# Adapter_USB3_to_M2_E.net
KiCad netlist of a schematic drawn in Altium Designer
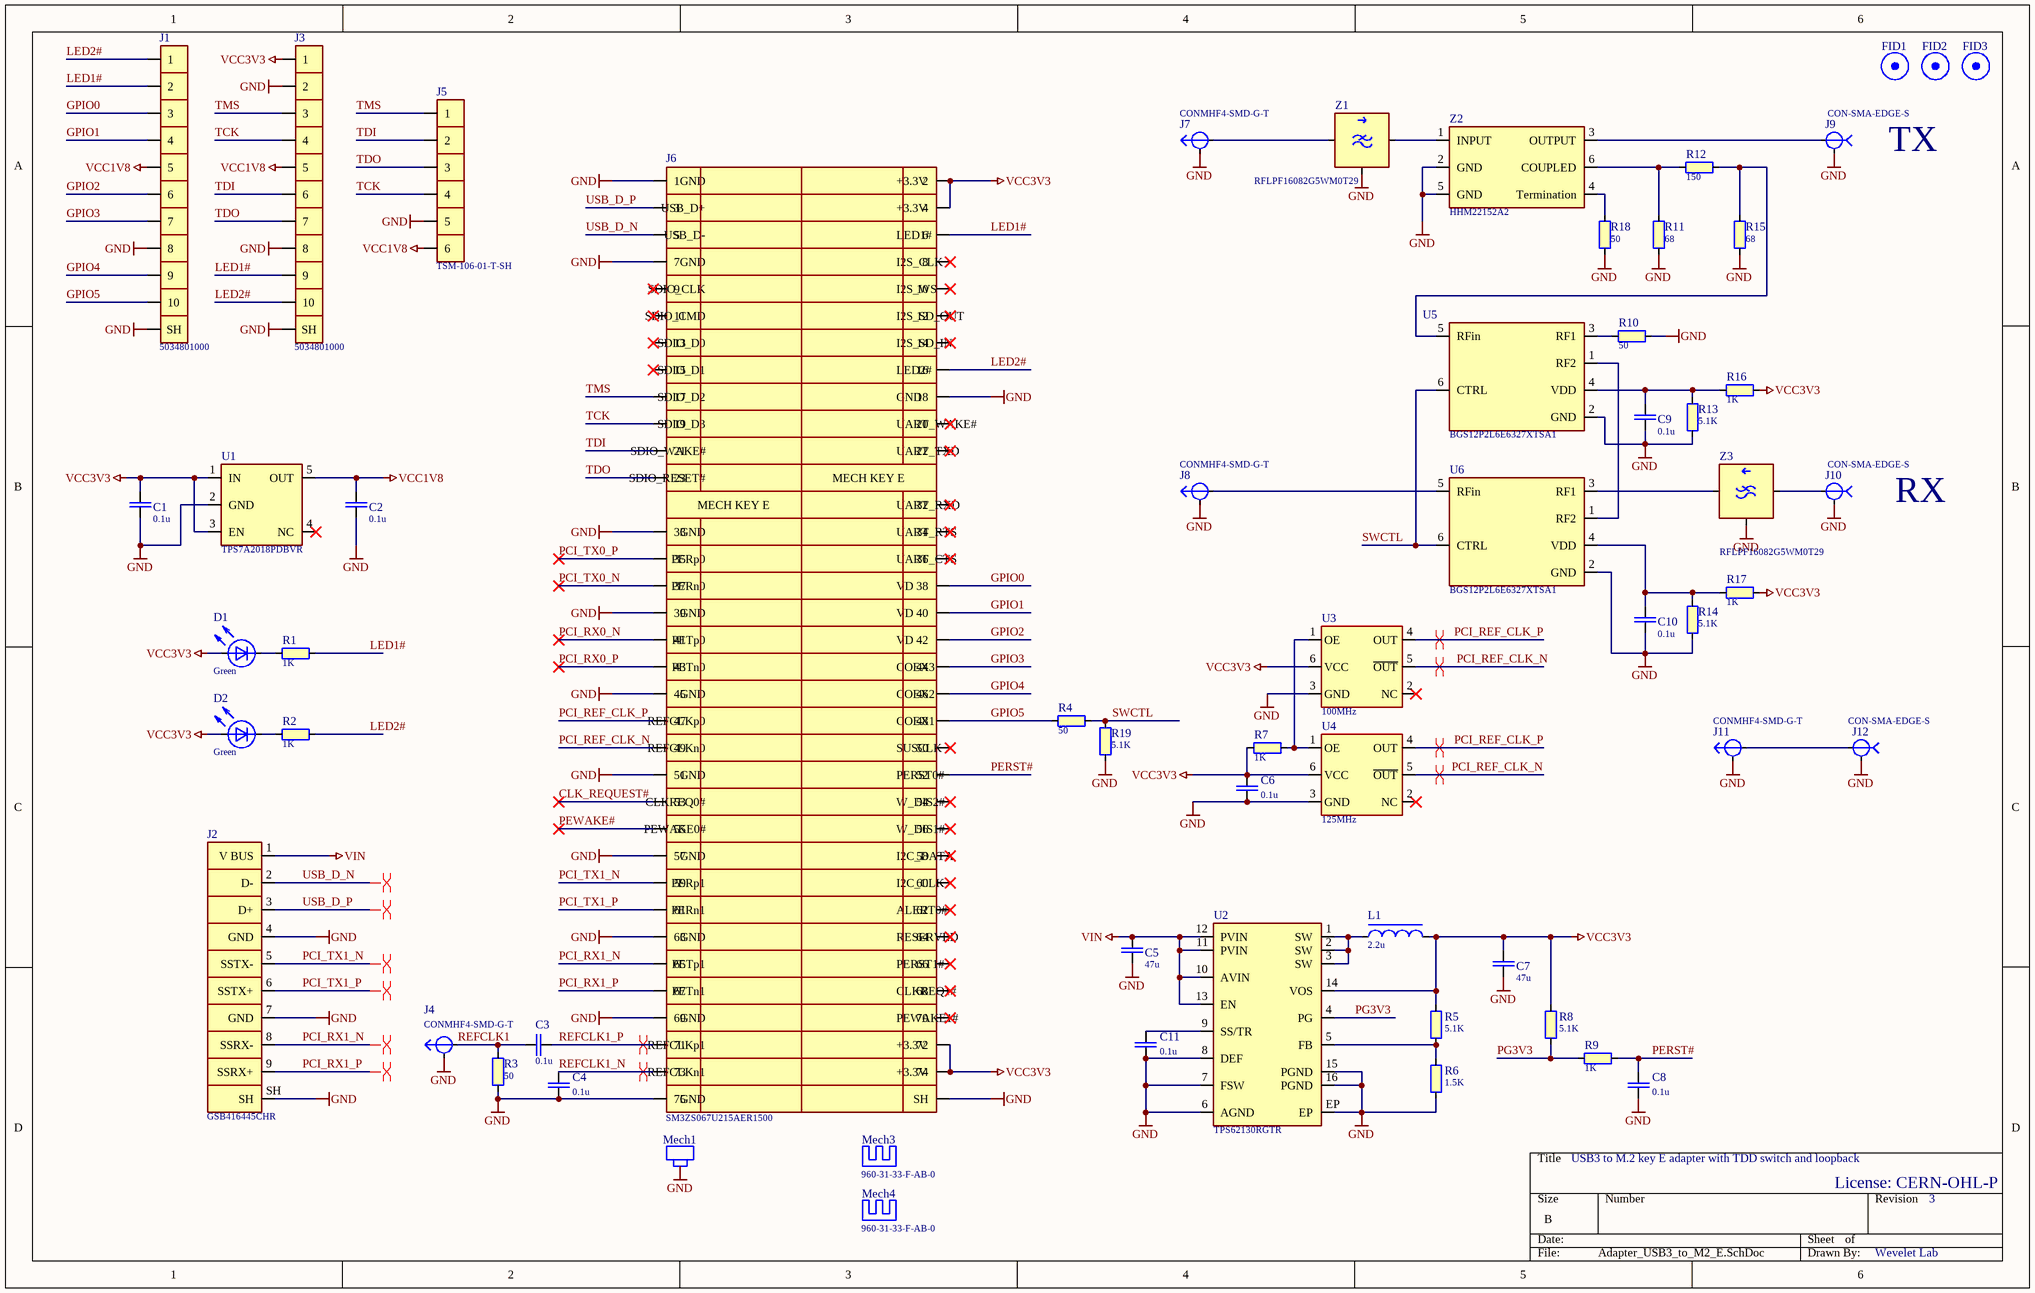
[diagram p0: Adapter_USB3_to_M2_E.SchDoc]

(export (version "E")
  (design (tool "Eeschema 10.0.6"))
  (components
    (comp (ref "C1")
      (value "0.1u")
      (footprint "CAPC100X50X55L25N")
      (description "Capacitor, 0.1u, 25V, 10%, X7R, 0402")
      (fields
        (field (name "MANUFACTURER") "Murata Electronics")
        (field (name "Comment") "GRM155R71E104KE14D")
      )
      (libsource (lib "Capacitors") (part "GRM155R71E104KE14D"))
    )
    (comp (ref "C2")
      (value "0.1u")
      (footprint "CAPC100X50X55L25N")
      (description "Capacitor, 0.1u, 25V, 10%, X7R, 0402")
      (fields
        (field (name "MANUFACTURER") "Murata Electronics")
        (field (name "Comment") "GRM155R71E104KE14D")
      )
      (libsource (lib "Capacitors") (part "GRM155R71E104KE14D"))
    )
    (comp (ref "C3")
      (value "0.1u")
      (footprint "CAPC100X50X55L25N")
      (description "Capacitor, 0.1u, 25V, 10%, X7R, 0402")
      (fields
        (field (name "MANUFACTURER") "Murata Electronics")
        (field (name "Comment") "GRM155R71E104KE14D")
      )
      (libsource (lib "Capacitors") (part "GRM155R71E104KE14D"))
    )
    (comp (ref "C4")
      (value "0.1u")
      (footprint "CAPC100X50X55L25N")
      (description "Capacitor, 0.1u, 25V, 10%, X7R, 0402")
      (fields
        (field (name "MANUFACTURER") "Murata Electronics")
        (field (name "Comment") "GRM155R71E104KE14D")
      )
      (libsource (lib "Capacitors") (part "GRM155R71E104KE14D"))
    )
    (comp (ref "C5")
      (value "47u")
      (footprint "CAPC160X80X100L40N")
      (description "Capacitor, 47u, 6.3V, 20%, X5R, 0603")
      (fields (field (name "Comment") "Cap-0603-X5R-6.3V-47u-20%"))
      (libsource (lib "Capacitors") (part "Cap-0603-X5R-6.3V-47u-20%"))
    )
    (comp (ref "C6")
      (value "0.1u")
      (footprint "CAPC100X50X55L25N")
      (description "Capacitor, 0.1u, 25V, 10%, X7R, 0402")
      (fields (field (name "Comment") "GRM155R71E104KE14D"))
      (libsource (lib "Capacitors") (part "GRM155R71E104KE14D"))
    )
    (comp (ref "C7")
      (value "47u")
      (footprint "CAPC160X80X100L40N")
      (description "Capacitor, 47u, 6.3V, 20%, X5R, 0603")
      (fields (field (name "Comment") "Cap-0603-X5R-6.3V-47u-20%"))
      (libsource (lib "Capacitors") (part "Cap-0603-X5R-6.3V-47u-20%"))
    )
    (comp (ref "C8")
      (value "0.1u")
      (footprint "CAPC100X50X55L25N")
      (description "Capacitor, 0.1u, 25V, 10%, X7R, 0402")
      (fields (field (name "Comment") "GRM155R71E104KE14D"))
      (libsource (lib "Capacitors") (part "GRM155R71E104KE14D"))
    )
    (comp (ref "C9")
      (value "0.1u")
      (footprint "CAPC100X50X55L25N")
      (description "Capacitor, 0.1u, 25V, 10%, X7R, 0402")
      (fields (field (name "Comment") "GRM155R71E104KE14D"))
      (libsource (lib "Capacitors") (part "GRM155R71E104KE14D"))
    )
    (comp (ref "C10")
      (value "0.1u")
      (footprint "CAPC100X50X55L25N")
      (description "Capacitor, 0.1u, 25V, 10%, X7R, 0402")
      (fields (field (name "Comment") "GRM155R71E104KE14D"))
      (libsource (lib "Capacitors") (part "GRM155R71E104KE14D"))
    )
    (comp (ref "C11")
      (value "0.1u")
      (footprint "CAPC100X50X55L25N")
      (description "Capacitor, 0.1u, 25V, 10%, X7R, 0402")
      (fields
        (field (name "MANUFACTURER") "Murata Electronics")
        (field (name "Comment") "GRM155R71E104KE14D")
      )
      (libsource (lib "Capacitors") (part "GRM155R71E104KE14D"))
    )
    (comp (ref "D1")
      (value "Green")
      (footprint "LEDC160X80X80L40N-Green")
      (description "LED Diode, Green, -30/+85, SMD0603")
      (fields (field (name "MANUFACTURER") "Lite-On Inc.") (field (name "Comment") "LTST-C190KGKT"))
      (libsource (lib "Diode_Transistor") (part "LTST-C190KGKT"))
    )
    (comp (ref "D2")
      (value "Green")
      (footprint "LEDC160X80X80L40N-Green")
      (description "LED Diode, Green, -30/+85, SMD0603")
      (fields (field (name "MANUFACTURER") "Lite-On Inc.") (field (name "Comment") "LTST-C190KGKT"))
      (libsource (lib "Diode_Transistor") (part "LTST-C190KGKT"))
    )
    (comp (ref "FID1")
      (value "Fiducial")
      (footprint "Fiducial_2D")
      (libsource (lib "Mech") (part "Fiducial"))
    )
    (comp (ref "FID2")
      (value "Fiducial")
      (footprint "Fiducial_2D")
      (libsource (lib "Mech") (part "Fiducial"))
    )
    (comp (ref "FID3")
      (value "Fiducial")
      (footprint "Fiducial_2D")
      (libsource (lib "Mech") (part "Fiducial"))
    )
    (comp (ref "J1")
      (value "5034801000")
      (footprint "MOLEX_5034801000")
      (description "Conn, FFC, 10 pins, 0.5mm, -40/+85, Right, SMD")
      (fields (field (name "MANUFACTURER") "Molex"))
      (libsource (lib "Connectors") (part "5034801000"))
    )
    (comp (ref "J2")
      (value "GSB416445CHR")
      (footprint "AMPHENOL_GSB416445CHR")
      (description "Conn, USB3.2 type A, -30/+85, Right, Trough Hole")
      (fields (field (name "MANUFACTURER") "Amphenol ICC"))
      (libsource (lib "Connectors") (part "GSB416445CHR"))
    )
    (comp (ref "J3")
      (value "5034801000")
      (footprint "MOLEX_5034801000")
      (description "Conn, FFC, 10 pins, 0.5mm, -40/+85, Right, SMD")
      (fields (field (name "MANUFACTURER") "Molex"))
      (libsource (lib "Connectors") (part "5034801000"))
    )
    (comp (ref "J4")
      (value "CONMHF4-SMD-G-T")
      (footprint "LINX_CONMHF4-SMD-G-T")
      (description "Conn, IPEX MHF4, Male Pin, 50 Ohm, -65/+165, SMD")
      (fields (field (name "MANUFACTURER") "Linx Technologies Inc."))
      (libsource (lib "Connectors") (part "CONMHF4-SMD-G-T"))
    )
    (comp (ref "J5")
      (value "TSM-106-01-T-SH")
      (footprint "SAMTEC_TSM-106-01-T-SH")
      (description "Conn, Header 6x1, 2.54mm,Right, Trough Hole")
      (fields (field (name "MANUFACTURER") "Samtec"))
      (libsource (lib "Connectors") (part "TSM-106-01-T-SH"))
    )
    (comp (ref "J6")
      (value "SM3ZS067U215AER1500")
      (footprint "JAE_SM3ZS067U215AER1500")
      (description "Conn M.2, Key E, -40/+80, SMD")
      (fields (field (name "MANUFACTURER") "JAE"))
      (libsource (lib "Connectors") (part "SM3ZS067U215AER1500"))
    )
    (comp (ref "J7")
      (value "CONMHF4-SMD-G-T")
      (footprint "LINX_CONMHF4-SMD-G-T")
      (description "Conn, IPEX MHF4, Male Pin, 50 Ohm, -65/+165, SMD")
      (fields (field (name "MANUFACTURER") "Linx Technologies Inc."))
      (libsource (lib "Connectors") (part "CONMHF4-SMD-G-T"))
    )
    (comp (ref "J8")
      (value "CONMHF4-SMD-G-T")
      (footprint "LINX_CONMHF4-SMD-G-T")
      (description "Conn, IPEX MHF4, Male Pin, 50 Ohm, -65/+165, SMD")
      (fields (field (name "MANUFACTURER") "Linx Technologies Inc."))
      (libsource (lib "Connectors") (part "CONMHF4-SMD-G-T"))
    )
    (comp (ref "J9")
      (value "CON-SMA-EDGE-S")
      (footprint "SSE_S01-SJEDM-11BS00")
      (description "Conn, Female Pin, 50 Ohm, SMA")
      (fields (field (name "MANUFACTURER") "RF Solutions"))
      (libsource (lib "Connectors") (part "S01-SJEDM-11BS00"))
    )
    (comp (ref "J10")
      (value "CON-SMA-EDGE-S")
      (footprint "SSE_S01-SJEDM-11BS00")
      (description "Conn, Female Pin, 50 Ohm, SMA")
      (fields (field (name "MANUFACTURER") "RF Solutions"))
      (libsource (lib "Connectors") (part "S01-SJEDM-11BS00"))
    )
    (comp (ref "J11")
      (value "CONMHF4-SMD-G-T")
      (footprint "LINX_CONMHF4-SMD-G-T")
      (description "Conn, IPEX MHF4, Male Pin, 50 Ohm, -65/+165, SMD")
      (fields (field (name "MANUFACTURER") "Linx Technologies Inc."))
      (libsource (lib "Connectors") (part "CONMHF4-SMD-G-T"))
    )
    (comp (ref "J12")
      (value "CON-SMA-EDGE-S")
      (footprint "SSE_S01-SJEDM-11BS00")
      (description "Conn, Female Pin, 50 Ohm, SMA")
      (fields (field (name "MANUFACTURER") "RF Solutions"))
      (libsource (lib "Connectors") (part "S01-SJEDM-11BS00"))
    )
    (comp (ref "L1")
      (value "2.2u")
      (footprint "IND_TAIYO_NRS5020")
      (description "Inductor, 2.2u, 2,9A, 42mOhm, +/-30%, -25/+125, SMD")
      (fields (field (name "MANUFACTURER") "Taiyo Yuden") (field (name "Comment") "NRS5020T2R2NMGJ"))
      (libsource (lib "Inductor_Transformer") (part "NRS5020T2R2NMGJ"))
    )
    (comp (ref "Mech1")
      (value "SM3ZS067U215-NUT1-R2500")
      (footprint "JAE_SM3ZS067U215-NUT1")
      (description "Mech, standoff, M2, 0.35 mm")
      (fields (field (name "MANUFACTURER") "JAE"))
      (libsource (lib "Mech") (part "SM3ZS067U215-NUT1-R2500"))
    )
    (comp (ref "Mech3")
      (value "960-31-33-F-AB-0")
      (footprint "WAKEFIELD_960-31-33-F-AB-0")
      (description "Mech, Heatsink, 31x33 mm, front, push pins")
      (fields (field (name "MANUFACTURER") "Wakefield"))
      (libsource (lib "MyLibrary") (part "960-31-33-F-AB-0"))
    )
    (comp (ref "Mech4")
      (value "960-31-33-F-AB-0")
      (footprint "WAKEFIELD_960-31-33-F-AB-0")
      (description "Mech, Heatsink, 31x33 mm, front, push pins")
      (fields (field (name "MANUFACTURER") "Wakefield"))
      (libsource (lib "MyLibrary") (part "960-31-33-F-AB-0"))
    )
    (comp (ref "R1")
      (value "1K")
      (footprint "RESC100X50X40L20N")
      (description "Resistor, 1K, 0.063W, 5%, 0402")
      (fields (field (name "Comment") "Res-0402-1K-5%"))
      (libsource (lib "") (part "Res-0402-1K-5%_2"))
    )
    (comp (ref "R2")
      (value "1K")
      (footprint "RESC100X50X40L20N")
      (description "Resistor, 1K, 0.063W, 5%, 0402")
      (fields (field (name "Comment") "Res-0402-1K-5%"))
      (libsource (lib "") (part "Res-0402-1K-5%_2"))
    )
    (comp (ref "R3")
      (value "50")
      (footprint "RESC100X50X40L20N")
      (description "Resistor, 50, 0.063W, 5%, 0402")
      (fields (field (name "Comment") "Res-0402-51-5%"))
      (libsource (lib "") (part "Res-0402-50-5%_2"))
    )
    (comp (ref "R4")
      (value "50")
      (footprint "RESC100X50X40L20N")
      (description "Resistor, 50, 0.063W, 5%, 0402")
      (fields (field (name "Comment") "Res-0402-51-5%"))
      (libsource (lib "Resistors") (part "Res-0402-50-5%"))
    )
    (comp (ref "R5")
      (value "5.1K")
      (footprint "RESC100X50X40L20N")
      (description "Resistor, 5.1K, 0.063W, 1%, 0402")
      (fields (field (name "Comment") "Res-0402-5.1K-1%"))
      (libsource (lib "Resistors") (part "Res-0402-5.1K-1%"))
    )
    (comp (ref "R6")
      (value "1.5K")
      (footprint "RESC100X50X40L20N")
      (description "Resistor, 1.5K, 0.063W, 1%, 0402")
      (fields (field (name "Comment") "Res-0402-1.5K-1%"))
      (libsource (lib "Resistors") (part "Res-0402-1.5K-1%"))
    )
    (comp (ref "R7")
      (value "1K")
      (footprint "RESC100X50X40L20N")
      (description "Resistor, 1K, 0.063W, 5%, 0402")
      (fields (field (name "Comment") "Res-0402-1K-5%"))
      (libsource (lib "") (part "Res-0402-1K-5%_1"))
    )
    (comp (ref "R8")
      (value "5.1K")
      (footprint "RESC100X50X40L20N")
      (description "Resistor, 5.1K, 0.063W, 1%, 0402")
      (fields (field (name "Comment") "Res-0402-5.1K-1%"))
      (libsource (lib "Resistors") (part "Res-0402-5.1K-1%"))
    )
    (comp (ref "R9")
      (value "1K")
      (footprint "RESC100X50X40L20N")
      (description "Resistor, 1K, 0.063W, 5%, 0402")
      (fields (field (name "Comment") "Res-0402-1K-5%"))
      (libsource (lib "") (part "Res-0402-1K-5%_1"))
    )
    (comp (ref "R10")
      (value "50")
      (footprint "RESC100X50X40L20N")
      (description "Resistor, 50, 0.063W, 5%, 0402")
      (fields (field (name "Comment") "Res-0402-51-5%"))
      (libsource (lib "Resistors") (part "Res-0402-50-5%"))
    )
    (comp (ref "R11")
      (value "68")
      (footprint "RESC100X50X40L20N")
      (description "Resistor, 68, 0.063W, 5%, 0402")
      (fields (field (name "Comment") "Res-0402-68-5%"))
      (libsource (lib "Resistors") (part "Res-0402-68-5%"))
    )
    (comp (ref "R12")
      (value "150")
      (footprint "RESC100X50X40L20N")
      (description "Resistor, 150, 0.063W, 5%, 0402")
      (fields (field (name "Comment") "Res-0402-150-5%"))
      (libsource (lib "Resistors") (part "Res-0402-150-5%"))
    )
    (comp (ref "R13")
      (value "5.1K")
      (footprint "RESC100X50X40L20N")
      (description "Resistor, 5.1K, 0.063W, 1%, 0402")
      (fields (field (name "Comment") "Res-0402-5.1K-1%"))
      (libsource (lib "Resistors") (part "Res-0402-5.1K-1%"))
    )
    (comp (ref "R14")
      (value "5.1K")
      (footprint "RESC100X50X40L20N")
      (description "Resistor, 5.1K, 0.063W, 1%, 0402")
      (fields (field (name "Comment") "Res-0402-5.1K-1%"))
      (libsource (lib "Resistors") (part "Res-0402-5.1K-1%"))
    )
    (comp (ref "R15")
      (value "68")
      (footprint "RESC100X50X40L20N")
      (description "Resistor, 68, 0.063W, 5%, 0402")
      (fields (field (name "Comment") "Res-0402-68-5%"))
      (libsource (lib "Resistors") (part "Res-0402-68-5%"))
    )
    (comp (ref "R16")
      (value "1K")
      (footprint "RESC100X50X40L20N")
      (description "Resistor, 1K, 0.063W, 5%, 0402")
      (fields (field (name "Comment") "Res-0402-1K-5%"))
      (libsource (lib "Resistors") (part "Res-0402-1K-5%"))
    )
    (comp (ref "R17")
      (value "1K")
      (footprint "RESC100X50X40L20N")
      (description "Resistor, 1K, 0.063W, 5%, 0402")
      (fields (field (name "Comment") "Res-0402-1K-5%"))
      (libsource (lib "Resistors") (part "Res-0402-1K-5%"))
    )
    (comp (ref "R18")
      (value "50")
      (footprint "RESC100X50X40L20N")
      (description "Resistor, 50, 0.063W, 5%, 0402")
      (fields (field (name "Comment") "Res-0402-51-5%"))
      (libsource (lib "") (part "Res-0402-50-5%_1"))
    )
    (comp (ref "R19")
      (value "5.1K")
      (footprint "RESC100X50X40L20N")
      (description "Resistor, 5.1K, 0.063W, 1%, 0402")
      (fields (field (name "Comment") "Res-0402-5.1K-1%"))
      (libsource (lib "Resistors") (part "Res-0402-5.1K-1%"))
    )
    (comp (ref "U1")
      (value "TPS7A2018PDBVR")
      (footprint "SOT23-5P95_280X145L45X40N")
      (description "IC, VolReg, DC/DC, 2.2/5.5V, 1.8V, 0.25A, -40/+125, 4-X2SON")
      (fields (field (name "MANUFACTURER") "Texas Instruments"))
      (libsource (lib "MyLibrary") (part "TPS7A2018PDBVR"))
    )
    (comp (ref "U2")
      (value "TPS62130RGTR")
      (footprint "QFN17P50_300X300X100L40X24T170N")
      (description "IC, DC/DC, Step-Down, 3-17/0.9-6V, 3A, -40/+85, QFN-16")
      (fields (field (name "MANUFACTURER") "Texas Instruments"))
      (libsource (lib "IC Power") (part "TPS62130RGTR"))
    )
    (comp (ref "U3")
      (value "100MHz")
      (footprint "ABRACON_AK2A")
      (description "Oscillators, 100MHz, 2.375/3.63V, 25ppm, -40/+85, SMD")
      (fields (field (name "MANUFACTURER") "ABRACON") (field (name "Comment") "AK2ADDF1-100.000T"))
      (libsource (lib "Resonators_Generator") (part "AK2ADDF1-100.000T"))
    )
    (comp (ref "U4")
      (value "125MHz")
      (footprint "EPCOS_SG3225VAN")
      (description "Oscillators, 125MHz, 2.5/3.3V, 30ppm, -40/+85, SMD")
      (fields
        (field (name "MANUFACTURER") "Diodes Incorporated")
        (field (name "Comment") "SG3225VAN 125.000000M-KEGA3")
      )
      (libsource (lib "Resonators_Generator") (part "SG3225VAN 125.000000M-KEGA3"))
    )
    (comp (ref "U5")
      (value "BGS12P2L6E6327XTSA1")
      (footprint "PSON6P40_110X70X32L20X20N")
      (description "IC, RF switch, SPDT, 50Ohm -40/+85, TSLP-6-4")
      (fields (field (name "MANUFACTURER") "Infineon Technologies"))
      (libsource (lib "IC Analog") (part "BGS12P2L6E6327XTSA1"))
    )
    (comp (ref "U6")
      (value "BGS12P2L6E6327XTSA1")
      (footprint "PSON6P40_110X70X32L20X20N")
      (description "IC, RF switch, SPDT, 50Ohm -40/+85, TSLP-6-4")
      (fields (field (name "MANUFACTURER") "Infineon Technologies"))
      (libsource (lib "IC Analog") (part "BGS12P2L6E6327XTSA1"))
    )
    (comp (ref "Z1")
      (value "RFLPF16082G5WM0T29")
      (footprint "WALSIN_RFLPF16082G5WM0T29")
      (description "Filter, 50Ohm, 2300-2690MHz, SMD")
      (fields (field (name "MANUFACTURER") "Walsin Tech Corp"))
      (libsource (lib "Inductor_Transformer") (part "RFLPF16082G5WM0T29"))
    )
    (comp (ref "Z2")
      (value "HHM22152A2")
      (footprint "TDK_HHM22152A2")
      (description "Signal Coupler, 450-3800MHz, -40/+105, SMD")
      (fields (field (name "MANUFACTURER") "TDK"))
      (libsource (lib "Inductor_Transformer") (part "HHM22152A2"))
    )
    (comp (ref "Z3")
      (value "RFLPF16082G5WM0T29")
      (footprint "WALSIN_RFLPF16082G5WM0T29")
      (description "Filter, 50Ohm, 2300-2690MHz, SMD")
      (fields (field (name "MANUFACTURER") "Walsin Tech Corp"))
      (libsource (lib "") (part "RFLPF16082G5WM0T29_1"))
    )
  )
  (nets
    (net (code "1") (name "/CLK_REQUEST#") (class "Default")
      (node (ref "J6") (pin "53") (pinfunction "53_53") (pintype "passive+no_connect"))
    )
    (net (code "2") (name "/GPIO0") (class "Default")
      (node (ref "J1") (pin "3") (pinfunction "3_3") (pintype "passive"))
      (node (ref "J6") (pin "38") (pinfunction "38_38") (pintype "passive"))
    )
    (net (code "3") (name "/GPIO1") (class "Default")
      (node (ref "J1") (pin "4") (pinfunction "4_4") (pintype "passive"))
      (node (ref "J6") (pin "40") (pinfunction "40_40") (pintype "passive"))
    )
    (net (code "4") (name "/GPIO2") (class "Default")
      (node (ref "J1") (pin "6") (pinfunction "6_6") (pintype "passive"))
      (node (ref "J6") (pin "42") (pinfunction "42_42") (pintype "passive"))
    )
    (net (code "5") (name "/GPIO3") (class "Default")
      (node (ref "J1") (pin "7") (pinfunction "7_7") (pintype "passive"))
      (node (ref "J6") (pin "44") (pinfunction "44_44") (pintype "passive"))
    )
    (net (code "6") (name "/GPIO4") (class "Default")
      (node (ref "J1") (pin "9") (pinfunction "9_9") (pintype "passive"))
      (node (ref "J6") (pin "46") (pinfunction "46_46") (pintype "passive"))
    )
    (net (code "7") (name "/GPIO5") (class "Default")
      (node (ref "J1") (pin "10") (pinfunction "10_10") (pintype "passive"))
      (node (ref "J6") (pin "48") (pinfunction "48_48") (pintype "passive"))
      (node (ref "R4") (pin "1") (pinfunction "1_1") (pintype "passive"))
    )
    (net (code "8") (name "/LED1#") (class "Default")
      (node (ref "J1") (pin "2") (pinfunction "2_2") (pintype "passive"))
      (node (ref "J3") (pin "9") (pinfunction "9_9") (pintype "passive"))
      (node (ref "J6") (pin "6") (pinfunction "6_6") (pintype "passive"))
      (node (ref "R1") (pin "2") (pinfunction "2_2") (pintype "passive"))
    )
    (net (code "9") (name "/LED2#") (class "Default")
      (node (ref "J1") (pin "1") (pinfunction "1_1") (pintype "passive"))
      (node (ref "J3") (pin "10") (pinfunction "10_10") (pintype "passive"))
      (node (ref "J6") (pin "16") (pinfunction "16_16") (pintype "passive"))
      (node (ref "R2") (pin "2") (pinfunction "2_2") (pintype "passive"))
    )
    (net (code "10") (name "/PCI_REF_CLK_N") (class "Default")
      (node (ref "J6") (pin "49") (pinfunction "49_49") (pintype "passive"))
      (node (ref "U3") (pin "5") (pinfunction "~{OUT}_5") (pintype "power_in"))
      (node (ref "U4") (pin "5") (pinfunction "~{OUT}_5") (pintype "power_in"))
    )
    (net (code "11") (name "/PCI_REF_CLK_P") (class "Default")
      (node (ref "J6") (pin "47") (pinfunction "47_47") (pintype "passive"))
      (node (ref "U3") (pin "4") (pinfunction "OUT_4") (pintype "power_in"))
      (node (ref "U4") (pin "4") (pinfunction "OUT_4") (pintype "power_in"))
    )
    (net (code "12") (name "/PCI_RX0_N") (class "Default")
      (node (ref "J6") (pin "41") (pinfunction "41_41") (pintype "passive+no_connect"))
    )
    (net (code "13") (name "/PCI_RX0_P") (class "Default")
      (node (ref "J6") (pin "43") (pinfunction "43_43") (pintype "passive+no_connect"))
    )
    (net (code "14") (name "/PCI_RX1_N") (class "Default")
      (node (ref "J2") (pin "8") (pinfunction "SSRX-_8") (pintype "passive"))
      (node (ref "J6") (pin "65") (pinfunction "65_65") (pintype "passive"))
    )
    (net (code "15") (name "/PCI_RX1_P") (class "Default")
      (node (ref "J2") (pin "9") (pinfunction "SSRX+_9") (pintype "passive"))
      (node (ref "J6") (pin "67") (pinfunction "67_67") (pintype "passive"))
    )
    (net (code "16") (name "/PCI_TX0_N") (class "Default")
      (node (ref "J6") (pin "37") (pinfunction "37_37") (pintype "passive+no_connect"))
    )
    (net (code "17") (name "/PCI_TX0_P") (class "Default")
      (node (ref "J6") (pin "35") (pinfunction "35_35") (pintype "passive+no_connect"))
    )
    (net (code "18") (name "/PCI_TX1_N") (class "Default")
      (node (ref "J2") (pin "5") (pinfunction "SSTX-_5") (pintype "passive"))
      (node (ref "J6") (pin "59") (pinfunction "59_59") (pintype "passive"))
    )
    (net (code "19") (name "/PCI_TX1_P") (class "Default")
      (node (ref "J2") (pin "6") (pinfunction "SSTX+_6") (pintype "passive"))
      (node (ref "J6") (pin "61") (pinfunction "61_61") (pintype "passive"))
    )
    (net (code "20") (name "/PERST#") (class "Default")
      (node (ref "C8") (pin "2") (pinfunction "2_2") (pintype "passive"))
      (node (ref "J6") (pin "52") (pinfunction "52_52") (pintype "passive"))
      (node (ref "R9") (pin "1") (pinfunction "1_1") (pintype "passive"))
    )
    (net (code "21") (name "/PEWAKE#") (class "Default")
      (node (ref "J6") (pin "55") (pinfunction "55_55") (pintype "passive+no_connect"))
    )
    (net (code "22") (name "/PG3V3") (class "Default")
      (node (ref "R8") (pin "1") (pinfunction "1_1") (pintype "passive"))
      (node (ref "R9") (pin "2") (pinfunction "2_2") (pintype "passive"))
      (node (ref "U2") (pin "4") (pinfunction "PG_4") (pintype "passive"))
    )
    (net (code "23") (name "/REFCLK1") (class "Default")
      (node (ref "C3") (pin "1") (pinfunction "1_1") (pintype "passive"))
      (node (ref "J4") (pin "1") (pinfunction "1_1") (pintype "passive"))
      (node (ref "R3") (pin "1") (pinfunction "1_1") (pintype "passive"))
    )
    (net (code "24") (name "/REFCLK1_N") (class "Default")
      (node (ref "C4") (pin "2") (pinfunction "2_2") (pintype "passive"))
      (node (ref "J6") (pin "73") (pinfunction "73_73") (pintype "passive"))
    )
    (net (code "25") (name "/REFCLK1_P") (class "Default")
      (node (ref "C3") (pin "2") (pinfunction "2_2") (pintype "passive"))
      (node (ref "J6") (pin "71") (pinfunction "71_71") (pintype "passive"))
    )
    (net (code "26") (name "/SWCTL") (class "Default")
      (node (ref "R19") (pin "2") (pinfunction "2_2") (pintype "passive"))
      (node (ref "R4") (pin "2") (pinfunction "2_2") (pintype "passive"))
      (node (ref "U5") (pin "6") (pinfunction "CTRL_6") (pintype "passive"))
      (node (ref "U6") (pin "6") (pinfunction "CTRL_6") (pintype "passive"))
    )
    (net (code "27") (name "/TCK") (class "Default")
      (node (ref "J3") (pin "4") (pinfunction "4_4") (pintype "passive"))
      (node (ref "J5") (pin "4") (pinfunction "4_4") (pintype "passive"))
      (node (ref "J6") (pin "19") (pinfunction "19_19") (pintype "passive"))
    )
    (net (code "28") (name "/TDI") (class "Default")
      (node (ref "J3") (pin "6") (pinfunction "6_6") (pintype "passive"))
      (node (ref "J5") (pin "2") (pinfunction "2_2") (pintype "passive"))
      (node (ref "J6") (pin "21") (pinfunction "21_21") (pintype "passive"))
    )
    (net (code "29") (name "/TDO") (class "Default")
      (node (ref "J3") (pin "7") (pinfunction "7_7") (pintype "passive"))
      (node (ref "J5") (pin "3") (pinfunction "3_3") (pintype "passive"))
      (node (ref "J6") (pin "23") (pinfunction "23_23") (pintype "passive"))
    )
    (net (code "30") (name "/TMS") (class "Default")
      (node (ref "J3") (pin "3") (pinfunction "3_3") (pintype "passive"))
      (node (ref "J5") (pin "1") (pinfunction "1_1") (pintype "passive"))
      (node (ref "J6") (pin "17") (pinfunction "17_17") (pintype "passive"))
    )
    (net (code "31") (name "/USB_D_N") (class "Default")
      (node (ref "J2") (pin "2") (pinfunction "D-_2") (pintype "passive"))
      (node (ref "J6") (pin "5") (pinfunction "5_5") (pintype "passive"))
    )
    (net (code "32") (name "/USB_D_P") (class "Default")
      (node (ref "J2") (pin "3") (pinfunction "D+_3") (pintype "passive"))
      (node (ref "J6") (pin "3") (pinfunction "3_3") (pintype "passive"))
    )
    (net (code "33") (name "GND") (class "Default")
      (node (ref "C1") (pin "1") (pinfunction "1_1") (pintype "passive"))
      (node (ref "C10") (pin "2") (pinfunction "2_2") (pintype "passive"))
      (node (ref "C11") (pin "1") (pinfunction "1_1") (pintype "passive"))
      (node (ref "C2") (pin "1") (pinfunction "1_1") (pintype "passive"))
      (node (ref "C4") (pin "1") (pinfunction "1_1") (pintype "passive"))
      (node (ref "C5") (pin "2") (pinfunction "2_2") (pintype "passive"))
      (node (ref "C6") (pin "1") (pinfunction "1_1") (pintype "passive"))
      (node (ref "C7") (pin "2") (pinfunction "2_2") (pintype "passive"))
      (node (ref "C8") (pin "1") (pinfunction "1_1") (pintype "passive"))
      (node (ref "C9") (pin "2") (pinfunction "2_2") (pintype "passive"))
      (node (ref "J1") (pin "8") (pinfunction "8_8") (pintype "passive"))
      (node (ref "J1") (pin "SH") (pinfunction "SH_SH") (pintype "passive"))
      (node (ref "J10") (pin "SH") (pinfunction "SH_SH") (pintype "passive"))
      (node (ref "J11") (pin "SH") (pinfunction "SH_SH") (pintype "passive"))
      (node (ref "J12") (pin "SH") (pinfunction "SH_SH") (pintype "passive"))
      (node (ref "J2") (pin "4") (pinfunction "GND_4") (pintype "passive"))
      (node (ref "J2") (pin "7") (pinfunction "GND_7") (pintype "passive"))
      (node (ref "J2") (pin "SH") (pinfunction "SH_SH") (pintype "passive"))
      (node (ref "J3") (pin "2") (pinfunction "2_2") (pintype "passive"))
      (node (ref "J3") (pin "8") (pinfunction "8_8") (pintype "passive"))
      (node (ref "J3") (pin "SH") (pinfunction "SH_SH") (pintype "passive"))
      (node (ref "J4") (pin "SH") (pinfunction "SH_SH") (pintype "passive"))
      (node (ref "J5") (pin "5") (pinfunction "5_5") (pintype "passive"))
      (node (ref "J6") (pin "1") (pinfunction "1_1") (pintype "passive"))
      (node (ref "J6") (pin "18") (pinfunction "18_18") (pintype "passive"))
      (node (ref "J6") (pin "33") (pinfunction "33_33") (pintype "passive"))
      (node (ref "J6") (pin "39") (pinfunction "39_39") (pintype "passive"))
      (node (ref "J6") (pin "45") (pinfunction "45_45") (pintype "passive"))
      (node (ref "J6") (pin "51") (pinfunction "51_51") (pintype "passive"))
      (node (ref "J6") (pin "57") (pinfunction "57_57") (pintype "passive"))
      (node (ref "J6") (pin "63") (pinfunction "63_63") (pintype "passive"))
      (node (ref "J6") (pin "69") (pinfunction "69_69") (pintype "passive"))
      (node (ref "J6") (pin "7") (pinfunction "7_7") (pintype "passive"))
      (node (ref "J6") (pin "75") (pinfunction "75_75") (pintype "passive"))
      (node (ref "J6") (pin "SH") (pinfunction "SH_SH") (pintype "passive"))
      (node (ref "J7") (pin "SH") (pinfunction "SH_SH") (pintype "passive"))
      (node (ref "J8") (pin "SH") (pinfunction "SH_SH") (pintype "passive"))
      (node (ref "J9") (pin "SH") (pinfunction "SH_SH") (pintype "passive"))
      (node (ref "Mech1") (pin "SH") (pinfunction "SH_SH") (pintype "passive"))
      (node (ref "R10") (pin "2") (pinfunction "2_2") (pintype "passive"))
      (node (ref "R11") (pin "2") (pinfunction "2_2") (pintype "passive"))
      (node (ref "R13") (pin "1") (pinfunction "1_1") (pintype "passive"))
      (node (ref "R14") (pin "1") (pinfunction "1_1") (pintype "passive"))
      (node (ref "R15") (pin "2") (pinfunction "2_2") (pintype "passive"))
      (node (ref "R18") (pin "1") (pinfunction "1_1") (pintype "passive"))
      (node (ref "R19") (pin "1") (pinfunction "1_1") (pintype "passive"))
      (node (ref "R3") (pin "2") (pinfunction "2_2") (pintype "passive"))
      (node (ref "R6") (pin "1") (pinfunction "1_1") (pintype "passive"))
      (node (ref "U1") (pin "2") (pinfunction "GND_2") (pintype "passive"))
      (node (ref "U2") (pin "15") (pinfunction "PGND_15") (pintype "passive"))
      (node (ref "U2") (pin "16") (pinfunction "PGND_16") (pintype "passive"))
      (node (ref "U2") (pin "6") (pinfunction "AGND_6") (pintype "passive"))
      (node (ref "U2") (pin "7") (pinfunction "FSW_7") (pintype "passive"))
      (node (ref "U2") (pin "8") (pinfunction "DEF_8") (pintype "passive"))
      (node (ref "U2") (pin "EP") (pinfunction "EP_EP") (pintype "passive"))
      (node (ref "U3") (pin "3") (pinfunction "GND_3") (pintype "power_in"))
      (node (ref "U4") (pin "3") (pinfunction "GND_3") (pintype "power_in"))
      (node (ref "U5") (pin "2") (pinfunction "GND_2") (pintype "passive"))
      (node (ref "U6") (pin "2") (pinfunction "GND_2") (pintype "passive"))
      (node (ref "Z1") (pin "2") (pinfunction "2_2") (pintype "passive"))
      (node (ref "Z2") (pin "2") (pinfunction "GND_2") (pintype "passive"))
      (node (ref "Z2") (pin "5") (pinfunction "GND_5") (pintype "passive"))
      (node (ref "Z3") (pin "2") (pinfunction "2_2") (pintype "passive"))
    )
    (net (code "34") (name "Net-(D1-PadC)") (class "Default")
      (node (ref "D1") (pin "C") (pinfunction "C_C") (pintype "passive"))
      (node (ref "R1") (pin "1") (pinfunction "1_1") (pintype "passive"))
    )
    (net (code "35") (name "Net-(D2-PadC)") (class "Default")
      (node (ref "D2") (pin "C") (pinfunction "C_C") (pintype "passive"))
      (node (ref "R2") (pin "1") (pinfunction "1_1") (pintype "passive"))
    )
    (net (code "36") (name "Net-(J7-Pad1)") (class "Default")
      (node (ref "J7") (pin "1") (pinfunction "1_1") (pintype "passive"))
      (node (ref "Z1") (pin "1") (pinfunction "1_1") (pintype "passive"))
    )
    (net (code "37") (name "Net-(J10-Pad1)") (class "Default")
      (node (ref "J10") (pin "1") (pinfunction "1_1") (pintype "passive"))
      (node (ref "Z3") (pin "1") (pinfunction "1_1") (pintype "passive"))
    )
    (net (code "38") (name "Net-(J11-Pad1)") (class "Default")
      (node (ref "J11") (pin "1") (pinfunction "1_1") (pintype "passive"))
      (node (ref "J12") (pin "1") (pinfunction "1_1") (pintype "passive"))
    )
    (net (code "39") (name "Net-(L1-Pad1)") (class "Default")
      (node (ref "L1") (pin "1") (pinfunction "1_1") (pintype "passive"))
      (node (ref "U2") (pin "1") (pinfunction "SW_1") (pintype "passive"))
      (node (ref "U2") (pin "2") (pinfunction "SW_2") (pintype "passive"))
      (node (ref "U2") (pin "3") (pinfunction "SW_3") (pintype "passive"))
    )
    (net (code "40") (name "Net-(U2-FB)") (class "Default")
      (node (ref "R5") (pin "1") (pinfunction "1_1") (pintype "passive"))
      (node (ref "R6") (pin "2") (pinfunction "2_2") (pintype "passive"))
      (node (ref "U2") (pin "5") (pinfunction "FB_5") (pintype "passive"))
    )
    (net (code "41") (name "Net-(U2-SS{slash}TR)") (class "Default")
      (node (ref "C11") (pin "2") (pinfunction "2_2") (pintype "passive"))
      (node (ref "U2") (pin "9") (pinfunction "SS/TR_9") (pintype "passive"))
    )
    (net (code "42") (name "Net-(U3-OE)") (class "Default")
      (node (ref "R7") (pin "1") (pinfunction "1_1") (pintype "passive"))
      (node (ref "U3") (pin "1") (pinfunction "OE_1") (pintype "power_in"))
      (node (ref "U4") (pin "1") (pinfunction "OE_1") (pintype "power_in"))
    )
    (net (code "43") (name "Net-(U5-RF1)") (class "Default")
      (node (ref "R10") (pin "1") (pinfunction "1_1") (pintype "passive"))
      (node (ref "U5") (pin "3") (pinfunction "RF1_3") (pintype "passive"))
    )
    (net (code "44") (name "Net-(U5-RF2)") (class "Default")
      (node (ref "U5") (pin "1") (pinfunction "RF2_1") (pintype "passive"))
      (node (ref "U6") (pin "1") (pinfunction "RF2_1") (pintype "passive"))
    )
    (net (code "45") (name "Net-(U5-RFin)") (class "Default")
      (node (ref "R12") (pin "1") (pinfunction "1_1") (pintype "passive"))
      (node (ref "R15") (pin "1") (pinfunction "1_1") (pintype "passive"))
      (node (ref "U5") (pin "5") (pinfunction "RFin_5") (pintype "passive"))
    )
    (net (code "46") (name "Net-(U5-VDD)") (class "Default")
      (node (ref "C9") (pin "1") (pinfunction "1_1") (pintype "passive"))
      (node (ref "R13") (pin "2") (pinfunction "2_2") (pintype "passive"))
      (node (ref "R16") (pin "1") (pinfunction "1_1") (pintype "passive"))
      (node (ref "U5") (pin "4") (pinfunction "VDD_4") (pintype "passive"))
    )
    (net (code "47") (name "Net-(U6-RF1)") (class "Default")
      (node (ref "U6") (pin "3") (pinfunction "RF1_3") (pintype "passive"))
      (node (ref "Z3") (pin "3") (pinfunction "3_3") (pintype "passive"))
    )
    (net (code "48") (name "Net-(U6-RFin)") (class "Default")
      (node (ref "J8") (pin "1") (pinfunction "1_1") (pintype "passive"))
      (node (ref "U6") (pin "5") (pinfunction "RFin_5") (pintype "passive"))
    )
    (net (code "49") (name "Net-(U6-VDD)") (class "Default")
      (node (ref "C10") (pin "1") (pinfunction "1_1") (pintype "passive"))
      (node (ref "R14") (pin "2") (pinfunction "2_2") (pintype "passive"))
      (node (ref "R17") (pin "1") (pinfunction "1_1") (pintype "passive"))
      (node (ref "U6") (pin "4") (pinfunction "VDD_4") (pintype "passive"))
    )
    (net (code "50") (name "Net-(Z2-COUPLED)") (class "Default")
      (node (ref "R11") (pin "1") (pinfunction "1_1") (pintype "passive"))
      (node (ref "R12") (pin "2") (pinfunction "2_2") (pintype "passive"))
      (node (ref "Z2") (pin "6") (pinfunction "COUPLED_6") (pintype "passive"))
    )
    (net (code "51") (name "Net-(Z2-INPUT)") (class "Default")
      (node (ref "Z1") (pin "3") (pinfunction "3_3") (pintype "passive"))
      (node (ref "Z2") (pin "1") (pinfunction "INPUT_1") (pintype "passive"))
    )
    (net (code "52") (name "Net-(Z2-OUTPUT)") (class "Default")
      (node (ref "J9") (pin "1") (pinfunction "1_1") (pintype "passive"))
      (node (ref "Z2") (pin "3") (pinfunction "OUTPUT_3") (pintype "passive"))
    )
    (net (code "53") (name "Net-(Z2-Termination)") (class "Default")
      (node (ref "R18") (pin "2") (pinfunction "2_2") (pintype "passive"))
      (node (ref "Z2") (pin "4") (pinfunction "Termination_4") (pintype "passive"))
    )
    (net (code "54") (name "VCC1V8") (class "Default")
      (node (ref "C2") (pin "2") (pinfunction "2_2") (pintype "passive"))
      (node (ref "J1") (pin "5") (pinfunction "5_5") (pintype "passive"))
      (node (ref "J3") (pin "5") (pinfunction "5_5") (pintype "passive"))
      (node (ref "J5") (pin "6") (pinfunction "6_6") (pintype "passive"))
      (node (ref "U1") (pin "5") (pinfunction "OUT_5") (pintype "passive"))
    )
    (net (code "55") (name "VCC3V3") (class "Default")
      (node (ref "C1") (pin "2") (pinfunction "2_2") (pintype "passive"))
      (node (ref "C6") (pin "2") (pinfunction "2_2") (pintype "passive"))
      (node (ref "C7") (pin "1") (pinfunction "1_1") (pintype "passive"))
      (node (ref "D1") (pin "A") (pinfunction "A_A") (pintype "passive"))
      (node (ref "D2") (pin "A") (pinfunction "A_A") (pintype "passive"))
      (node (ref "J3") (pin "1") (pinfunction "1_1") (pintype "passive"))
      (node (ref "J6") (pin "2") (pinfunction "2_2") (pintype "passive"))
      (node (ref "J6") (pin "4") (pinfunction "4_4") (pintype "passive"))
      (node (ref "J6") (pin "72") (pinfunction "72_72") (pintype "passive"))
      (node (ref "J6") (pin "74") (pinfunction "74_74") (pintype "passive"))
      (node (ref "L1") (pin "2") (pinfunction "2_2") (pintype "passive"))
      (node (ref "R16") (pin "2") (pinfunction "2_2") (pintype "passive"))
      (node (ref "R17") (pin "2") (pinfunction "2_2") (pintype "passive"))
      (node (ref "R5") (pin "2") (pinfunction "2_2") (pintype "passive"))
      (node (ref "R7") (pin "2") (pinfunction "2_2") (pintype "passive"))
      (node (ref "R8") (pin "2") (pinfunction "2_2") (pintype "passive"))
      (node (ref "U1") (pin "1") (pinfunction "IN_1") (pintype "passive"))
      (node (ref "U1") (pin "3") (pinfunction "EN_3") (pintype "passive"))
      (node (ref "U2") (pin "14") (pinfunction "VOS_14") (pintype "passive"))
      (node (ref "U3") (pin "6") (pinfunction "VCC_6") (pintype "power_in"))
      (node (ref "U4") (pin "6") (pinfunction "VCC_6") (pintype "power_in"))
    )
    (net (code "56") (name "VIN") (class "Default")
      (node (ref "C5") (pin "1") (pinfunction "1_1") (pintype "passive"))
      (node (ref "J2") (pin "1") (pinfunction "V_BUS_1") (pintype "power_in"))
      (node (ref "U2") (pin "10") (pinfunction "AVIN_10") (pintype "passive"))
      (node (ref "U2") (pin "11") (pinfunction "PVIN_11") (pintype "passive"))
      (node (ref "U2") (pin "12") (pinfunction "PVIN_12") (pintype "passive"))
      (node (ref "U2") (pin "13") (pinfunction "EN_13") (pintype "passive"))
    )
    (net (code "57") (name "unconnected-(J6-Pad8)") (class "Default")
      (node (ref "J6") (pin "8") (pinfunction "8_8") (pintype "passive+no_connect"))
    )
    (net (code "58") (name "unconnected-(J6-Pad9)") (class "Default")
      (node (ref "J6") (pin "9") (pinfunction "9_9") (pintype "passive+no_connect"))
    )
    (net (code "59") (name "unconnected-(J6-Pad10)") (class "Default")
      (node (ref "J6") (pin "10") (pinfunction "10_10") (pintype "passive+no_connect"))
    )
    (net (code "60") (name "unconnected-(J6-Pad11)") (class "Default")
      (node (ref "J6") (pin "11") (pinfunction "11_11") (pintype "passive+no_connect"))
    )
    (net (code "61") (name "unconnected-(J6-Pad12)") (class "Default")
      (node (ref "J6") (pin "12") (pinfunction "12_12") (pintype "passive+no_connect"))
    )
    (net (code "62") (name "unconnected-(J6-Pad13)") (class "Default")
      (node (ref "J6") (pin "13") (pinfunction "13_13") (pintype "passive+no_connect"))
    )
    (net (code "63") (name "unconnected-(J6-Pad14)") (class "Default")
      (node (ref "J6") (pin "14") (pinfunction "14_14") (pintype "passive+no_connect"))
    )
    (net (code "64") (name "unconnected-(J6-Pad15)") (class "Default")
      (node (ref "J6") (pin "15") (pinfunction "15_15") (pintype "passive+no_connect"))
    )
    (net (code "65") (name "unconnected-(J6-Pad20)") (class "Default")
      (node (ref "J6") (pin "20") (pinfunction "20_20") (pintype "passive+no_connect"))
    )
    (net (code "66") (name "unconnected-(J6-Pad22)") (class "Default")
      (node (ref "J6") (pin "22") (pinfunction "22_22") (pintype "passive+no_connect"))
    )
    (net (code "67") (name "unconnected-(J6-Pad32)") (class "Default")
      (node (ref "J6") (pin "32") (pinfunction "32_32") (pintype "passive+no_connect"))
    )
    (net (code "68") (name "unconnected-(J6-Pad34)") (class "Default")
      (node (ref "J6") (pin "34") (pinfunction "34_34") (pintype "passive+no_connect"))
    )
    (net (code "69") (name "unconnected-(J6-Pad36)") (class "Default")
      (node (ref "J6") (pin "36") (pinfunction "36_36") (pintype "passive+no_connect"))
    )
    (net (code "70") (name "unconnected-(J6-Pad50)") (class "Default")
      (node (ref "J6") (pin "50") (pinfunction "50_50") (pintype "passive+no_connect"))
    )
    (net (code "71") (name "unconnected-(J6-Pad54)") (class "Default")
      (node (ref "J6") (pin "54") (pinfunction "54_54") (pintype "passive+no_connect"))
    )
    (net (code "72") (name "unconnected-(J6-Pad56)") (class "Default")
      (node (ref "J6") (pin "56") (pinfunction "56_56") (pintype "passive+no_connect"))
    )
    (net (code "73") (name "unconnected-(J6-Pad58)") (class "Default")
      (node (ref "J6") (pin "58") (pinfunction "58_58") (pintype "passive+no_connect"))
    )
    (net (code "74") (name "unconnected-(J6-Pad60)") (class "Default")
      (node (ref "J6") (pin "60") (pinfunction "60_60") (pintype "passive+no_connect"))
    )
    (net (code "75") (name "unconnected-(J6-Pad62)") (class "Default")
      (node (ref "J6") (pin "62") (pinfunction "62_62") (pintype "passive+no_connect"))
    )
    (net (code "76") (name "unconnected-(J6-Pad64)") (class "Default")
      (node (ref "J6") (pin "64") (pinfunction "64_64") (pintype "passive+no_connect"))
    )
    (net (code "77") (name "unconnected-(J6-Pad66)") (class "Default")
      (node (ref "J6") (pin "66") (pinfunction "66_66") (pintype "passive+no_connect"))
    )
    (net (code "78") (name "unconnected-(J6-Pad68)") (class "Default")
      (node (ref "J6") (pin "68") (pinfunction "68_68") (pintype "passive+no_connect"))
    )
    (net (code "79") (name "unconnected-(J6-Pad70)") (class "Default")
      (node (ref "J6") (pin "70") (pinfunction "70_70") (pintype "passive+no_connect"))
    )
    (net (code "80") (name "unconnected-(Mech3-PadMH)") (class "Default")
      (node (ref "Mech3") (pin "MH") (pinfunction "MH_MH") (pintype "passive"))
    )
    (net (code "81") (name "unconnected-(Mech4-PadMH)") (class "Default")
      (node (ref "Mech4") (pin "MH") (pinfunction "MH_MH") (pintype "passive"))
    )
    (net (code "82") (name "unconnected-(U1-NC-Pad4)") (class "Default")
      (node (ref "U1") (pin "4") (pinfunction "NC_4") (pintype "passive+no_connect"))
    )
    (net (code "83") (name "unconnected-(U3-NC-Pad2)") (class "Default")
      (node (ref "U3") (pin "2") (pinfunction "NC_2") (pintype "power_in+no_connect"))
    )
    (net (code "84") (name "unconnected-(U4-NC-Pad2)") (class "Default")
      (node (ref "U4") (pin "2") (pinfunction "NC_2") (pintype "power_in+no_connect"))
    )
  )
)
